# NightOwl_v5.net
KiCad netlist of a schematic drawn in EAGLE
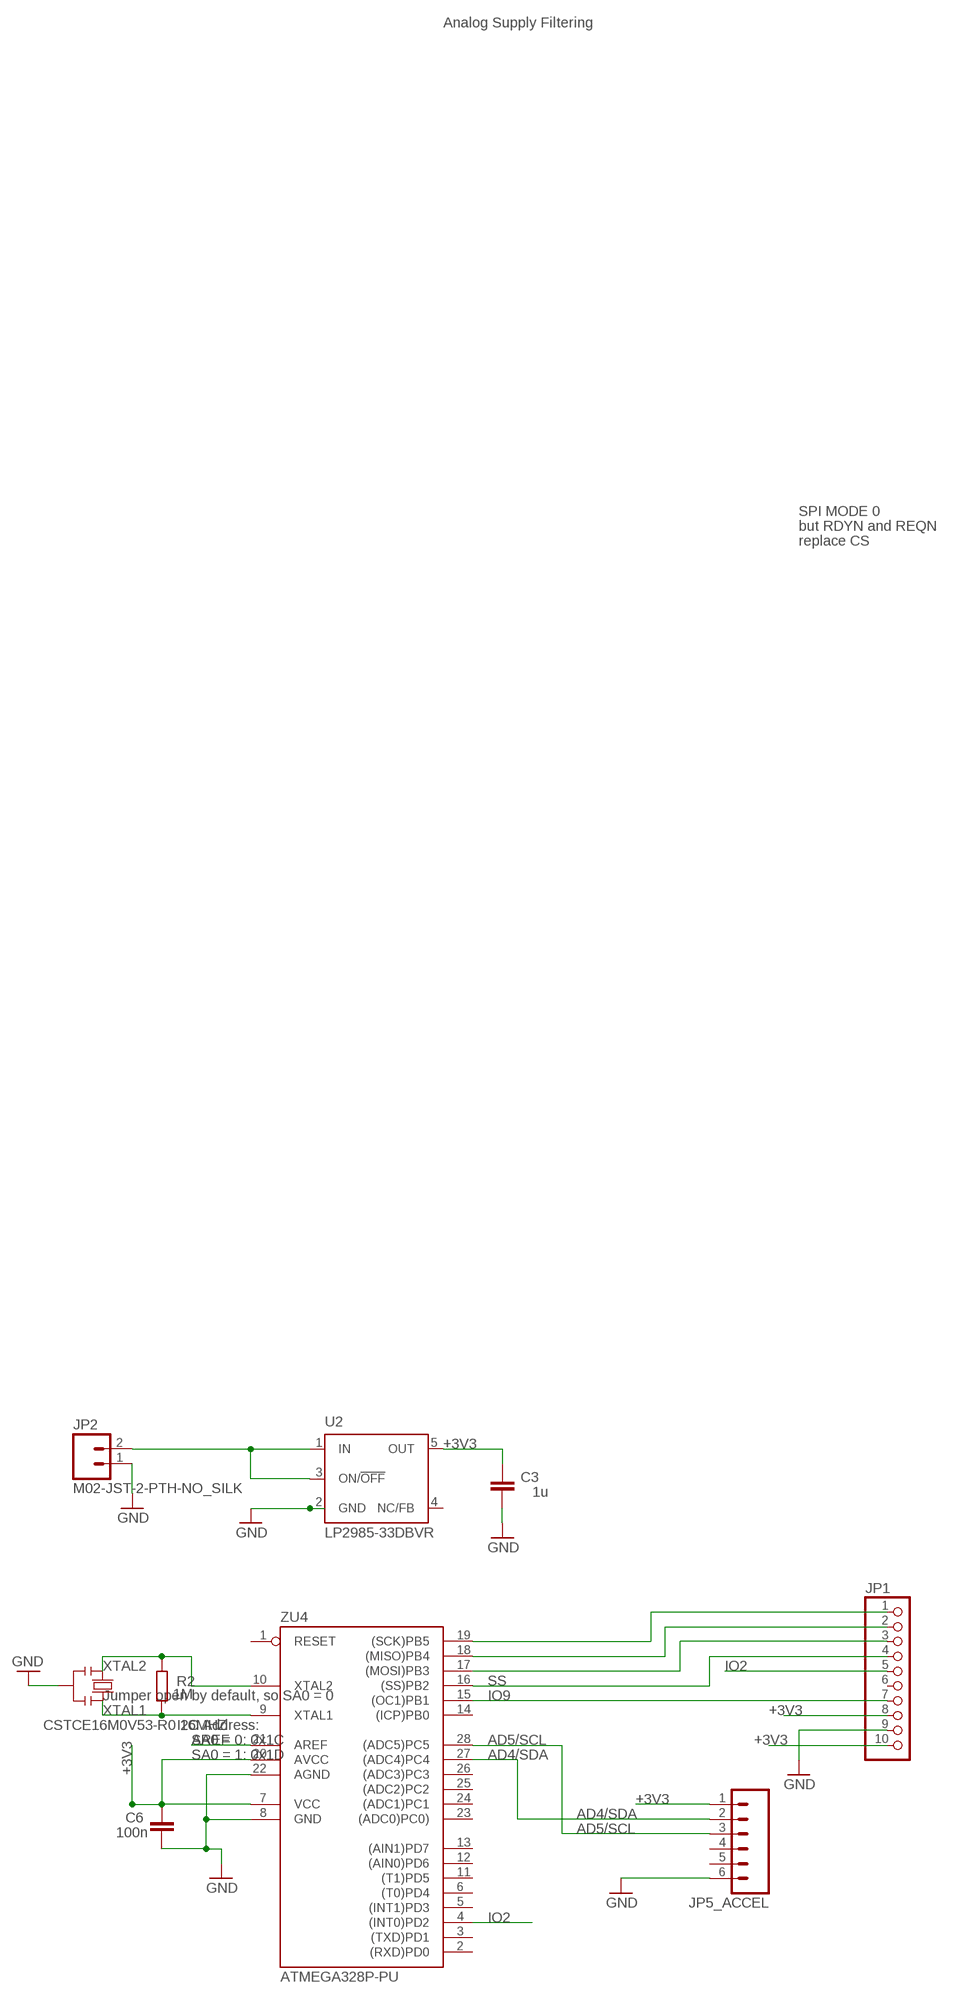
[diagram p0: schematic, sheet 1]

(export (version "E")
  (design (tool "Eeschema 10.0.6"))
  (components
    (comp (ref "C3")
      (value "1u")
      (footprint "eagle-import:C0603-ROUND")
      (libsource (lib "eagle-import") (part "C-EU0603-RND"))
    )
    (comp (ref "C6")
      (value "100n")
      (footprint "eagle-import:C0603-ROUND")
      (libsource (lib "eagle-import") (part "C-EU0603-RND"))
    )
    (comp (ref "JP1")
      (value "HEADER-1X1070MIL")
      (footprint "eagle-import:1X10_ROUND70")
      (libsource (lib "eagle-import") (part "HEADER-1X1070MIL"))
    )
    (comp (ref "JP2")
      (value "M02-JST-2-PTH-NO_SILK")
      (footprint "eagle-import:JST-2-PTH-NS")
      (libsource (lib "eagle-import") (part "M02-JST-2-PTH-NO_SILK"))
    )
    (comp (ref "JP5_ACCEL")
      (value "M06SIP")
      (footprint "eagle-import:1X06")
      (libsource (lib "eagle-import") (part "M06SIP"))
    )
    (comp (ref "R2")
      (value "1M")
      (footprint "eagle-import:R0603-ROUND")
      (libsource (lib "eagle-import") (part "R-EU_R0603"))
    )
    (comp (ref "U2")
      (value "LP2985-33DBVR")
      (footprint "eagle-import:SOT23-DBV")
      (libsource (lib "eagle-import") (part "LP2985-XXDBVR33"))
    )
    (comp (ref "Y2")
      (value "CSTCE16M0V53-R0 16MHZ")
      (footprint "eagle-import:RESONATOR")
      (libsource (lib "eagle-import") (part "RESONATORMU"))
    )
    (comp (ref "ZU4")
      (value "ATMEGA328P-PU")
      (footprint "eagle-import:DIL28-3")
      (libsource (lib "eagle-import") (part "ATMEGA328P-PU"))
    )
  )
  (nets
    (net (code "1") (name "/+3V3") (class "Default")
      (node (ref "C3") (pin "2") (pinfunction "2_2") (pintype "passive"))
      (node (ref "C6") (pin "2") (pinfunction "2_2") (pintype "passive"))
      (node (ref "JP1") (pin "10") (pinfunction "10_10") (pintype "passive"))
      (node (ref "JP1") (pin "8") (pinfunction "8_8") (pintype "passive"))
      (node (ref "JP5_ACCEL") (pin "1") (pinfunction "1_1") (pintype "passive"))
      (node (ref "U2") (pin "5") (pinfunction "OUT_5") (pintype "passive"))
      (node (ref "ZU4") (pin "20") (pinfunction "AVCC_20") (pintype "power_in"))
      (node (ref "ZU4") (pin "7") (pinfunction "VCC_7") (pintype "power_in"))
    )
    (net (code "2") (name "/AD4{slash}SDA") (class "Default")
      (node (ref "JP5_ACCEL") (pin "2") (pinfunction "2_2") (pintype "passive"))
      (node (ref "ZU4") (pin "27") (pinfunction "(ADC4)PC4_27") (pintype "bidirectional"))
    )
    (net (code "3") (name "/AD5{slash}SCL") (class "Default")
      (node (ref "JP5_ACCEL") (pin "3") (pinfunction "3_3") (pintype "passive"))
      (node (ref "ZU4") (pin "28") (pinfunction "(ADC5)PC5_28") (pintype "bidirectional"))
    )
    (net (code "4") (name "/AREF") (class "Default")
      (node (ref "ZU4") (pin "21") (pinfunction "AREF_21") (pintype "passive"))
    )
    (net (code "5") (name "/IO2") (class "Default")
      (node (ref "JP1") (pin "5") (pinfunction "5_5") (pintype "passive"))
      (node (ref "ZU4") (pin "4") (pinfunction "(INT0)PD2_4") (pintype "bidirectional"))
    )
    (net (code "6") (name "/IO9") (class "Default")
      (node (ref "JP1") (pin "7") (pinfunction "7_7") (pintype "passive"))
      (node (ref "ZU4") (pin "15") (pinfunction "(OC1)PB1_15") (pintype "bidirectional"))
    )
    (net (code "7") (name "/SS") (class "Default")
      (node (ref "JP1") (pin "4") (pinfunction "4_4") (pintype "passive"))
      (node (ref "ZU4") (pin "16") (pinfunction "(SS)PB2_16") (pintype "bidirectional"))
    )
    (net (code "8") (name "/XTAL1") (class "Default")
      (node (ref "R2") (pin "1") (pinfunction "1_1") (pintype "passive"))
      (node (ref "Y2") (pin "3") (pinfunction "3_3") (pintype "passive"))
      (node (ref "ZU4") (pin "9") (pinfunction "XTAL1_9") (pintype "bidirectional"))
    )
    (net (code "9") (name "/XTAL2") (class "Default")
      (node (ref "R2") (pin "2") (pinfunction "2_2") (pintype "passive"))
      (node (ref "Y2") (pin "1") (pinfunction "1_1") (pintype "passive"))
      (node (ref "ZU4") (pin "10") (pinfunction "XTAL2_10") (pintype "bidirectional"))
    )
    (net (code "10") (name "GND") (class "Default")
      (node (ref "C3") (pin "1") (pinfunction "1_1") (pintype "passive"))
      (node (ref "C6") (pin "1") (pinfunction "1_1") (pintype "passive"))
      (node (ref "JP1") (pin "9") (pinfunction "9_9") (pintype "passive"))
      (node (ref "JP2") (pin "1") (pinfunction "1_1") (pintype "passive"))
      (node (ref "JP5_ACCEL") (pin "6") (pinfunction "6_6") (pintype "passive"))
      (node (ref "U2") (pin "2") (pinfunction "GND_2") (pintype "power_in"))
      (node (ref "Y2") (pin "2") (pinfunction "2_2") (pintype "passive"))
      (node (ref "ZU4") (pin "22") (pinfunction "AGND_22") (pintype "power_in"))
      (node (ref "ZU4") (pin "8") (pinfunction "GND_8") (pintype "power_in"))
    )
    (net (code "11") (name "Net-(U2-IN)") (class "Default")
      (node (ref "JP2") (pin "2") (pinfunction "2_2") (pintype "passive"))
      (node (ref "U2") (pin "1") (pinfunction "IN_1") (pintype "input"))
      (node (ref "U2") (pin "3") (pinfunction "ON/~{OFF}_3") (pintype "input"))
    )
    (net (code "12") (name "Net-(ZU4-(MISO)PB4)") (class "Default")
      (node (ref "JP1") (pin "2") (pinfunction "2_2") (pintype "passive"))
      (node (ref "ZU4") (pin "18") (pinfunction "(MISO)PB4_18") (pintype "bidirectional"))
    )
    (net (code "13") (name "Net-(ZU4-(MOSI)PB3)") (class "Default")
      (node (ref "JP1") (pin "3") (pinfunction "3_3") (pintype "passive"))
      (node (ref "ZU4") (pin "17") (pinfunction "(MOSI)PB3_17") (pintype "bidirectional"))
    )
    (net (code "14") (name "Net-(ZU4-(SCK)PB5)") (class "Default")
      (node (ref "JP1") (pin "1") (pinfunction "1_1") (pintype "passive"))
      (node (ref "ZU4") (pin "19") (pinfunction "(SCK)PB5_19") (pintype "bidirectional"))
    )
    (net (code "15") (name "unconnected-(JP1-Pad6)") (class "Default")
      (node (ref "JP1") (pin "6") (pinfunction "6_6") (pintype "passive"))
    )
    (net (code "16") (name "unconnected-(JP5_ACCEL-Pad4)") (class "Default")
      (node (ref "JP5_ACCEL") (pin "4") (pinfunction "4_4") (pintype "passive"))
    )
    (net (code "17") (name "unconnected-(JP5_ACCEL-Pad5)") (class "Default")
      (node (ref "JP5_ACCEL") (pin "5") (pinfunction "5_5") (pintype "passive"))
    )
    (net (code "18") (name "unconnected-(U2-NC{slash}FB-Pad4)") (class "Default")
      (node (ref "U2") (pin "4") (pinfunction "NC/FB_4") (pintype "passive"))
    )
    (net (code "19") (name "unconnected-(ZU4-(ADC0)PC0)-Pad23)") (class "Default")
      (node (ref "ZU4") (pin "23") (pinfunction "(ADC0)PC0)_23") (pintype "bidirectional"))
    )
    (net (code "20") (name "unconnected-(ZU4-(ADC1)PC1-Pad24)") (class "Default")
      (node (ref "ZU4") (pin "24") (pinfunction "(ADC1)PC1_24") (pintype "bidirectional"))
    )
    (net (code "21") (name "unconnected-(ZU4-(ADC2)PC2-Pad25)") (class "Default")
      (node (ref "ZU4") (pin "25") (pinfunction "(ADC2)PC2_25") (pintype "bidirectional"))
    )
    (net (code "22") (name "unconnected-(ZU4-(ADC3)PC3-Pad26)") (class "Default")
      (node (ref "ZU4") (pin "26") (pinfunction "(ADC3)PC3_26") (pintype "bidirectional"))
    )
    (net (code "23") (name "unconnected-(ZU4-(AIN0)PD6-Pad12)") (class "Default")
      (node (ref "ZU4") (pin "12") (pinfunction "(AIN0)PD6_12") (pintype "bidirectional"))
    )
    (net (code "24") (name "unconnected-(ZU4-(AIN1)PD7-Pad13)") (class "Default")
      (node (ref "ZU4") (pin "13") (pinfunction "(AIN1)PD7_13") (pintype "bidirectional"))
    )
    (net (code "25") (name "unconnected-(ZU4-(ICP)PB0-Pad14)") (class "Default")
      (node (ref "ZU4") (pin "14") (pinfunction "(ICP)PB0_14") (pintype "bidirectional"))
    )
    (net (code "26") (name "unconnected-(ZU4-(INT1)PD3-Pad5)") (class "Default")
      (node (ref "ZU4") (pin "5") (pinfunction "(INT1)PD3_5") (pintype "bidirectional"))
    )
    (net (code "27") (name "unconnected-(ZU4-(RXD)PD0-Pad2)") (class "Default")
      (node (ref "ZU4") (pin "2") (pinfunction "(RXD)PD0_2") (pintype "bidirectional"))
    )
    (net (code "28") (name "unconnected-(ZU4-(T0)PD4-Pad6)") (class "Default")
      (node (ref "ZU4") (pin "6") (pinfunction "(T0)PD4_6") (pintype "bidirectional"))
    )
    (net (code "29") (name "unconnected-(ZU4-(T1)PD5-Pad11)") (class "Default")
      (node (ref "ZU4") (pin "11") (pinfunction "(T1)PD5_11") (pintype "bidirectional"))
    )
    (net (code "30") (name "unconnected-(ZU4-(TXD)PD1-Pad3)") (class "Default")
      (node (ref "ZU4") (pin "3") (pinfunction "(TXD)PD1_3") (pintype "bidirectional"))
    )
    (net (code "31") (name "unconnected-(ZU4-RESET-Pad1)") (class "Default")
      (node (ref "ZU4") (pin "1") (pinfunction "RESET_1") (pintype "input"))
    )
  )
)
